# 11_USB_2.net
KiCad netlist of a schematic drawn in Altium Designer
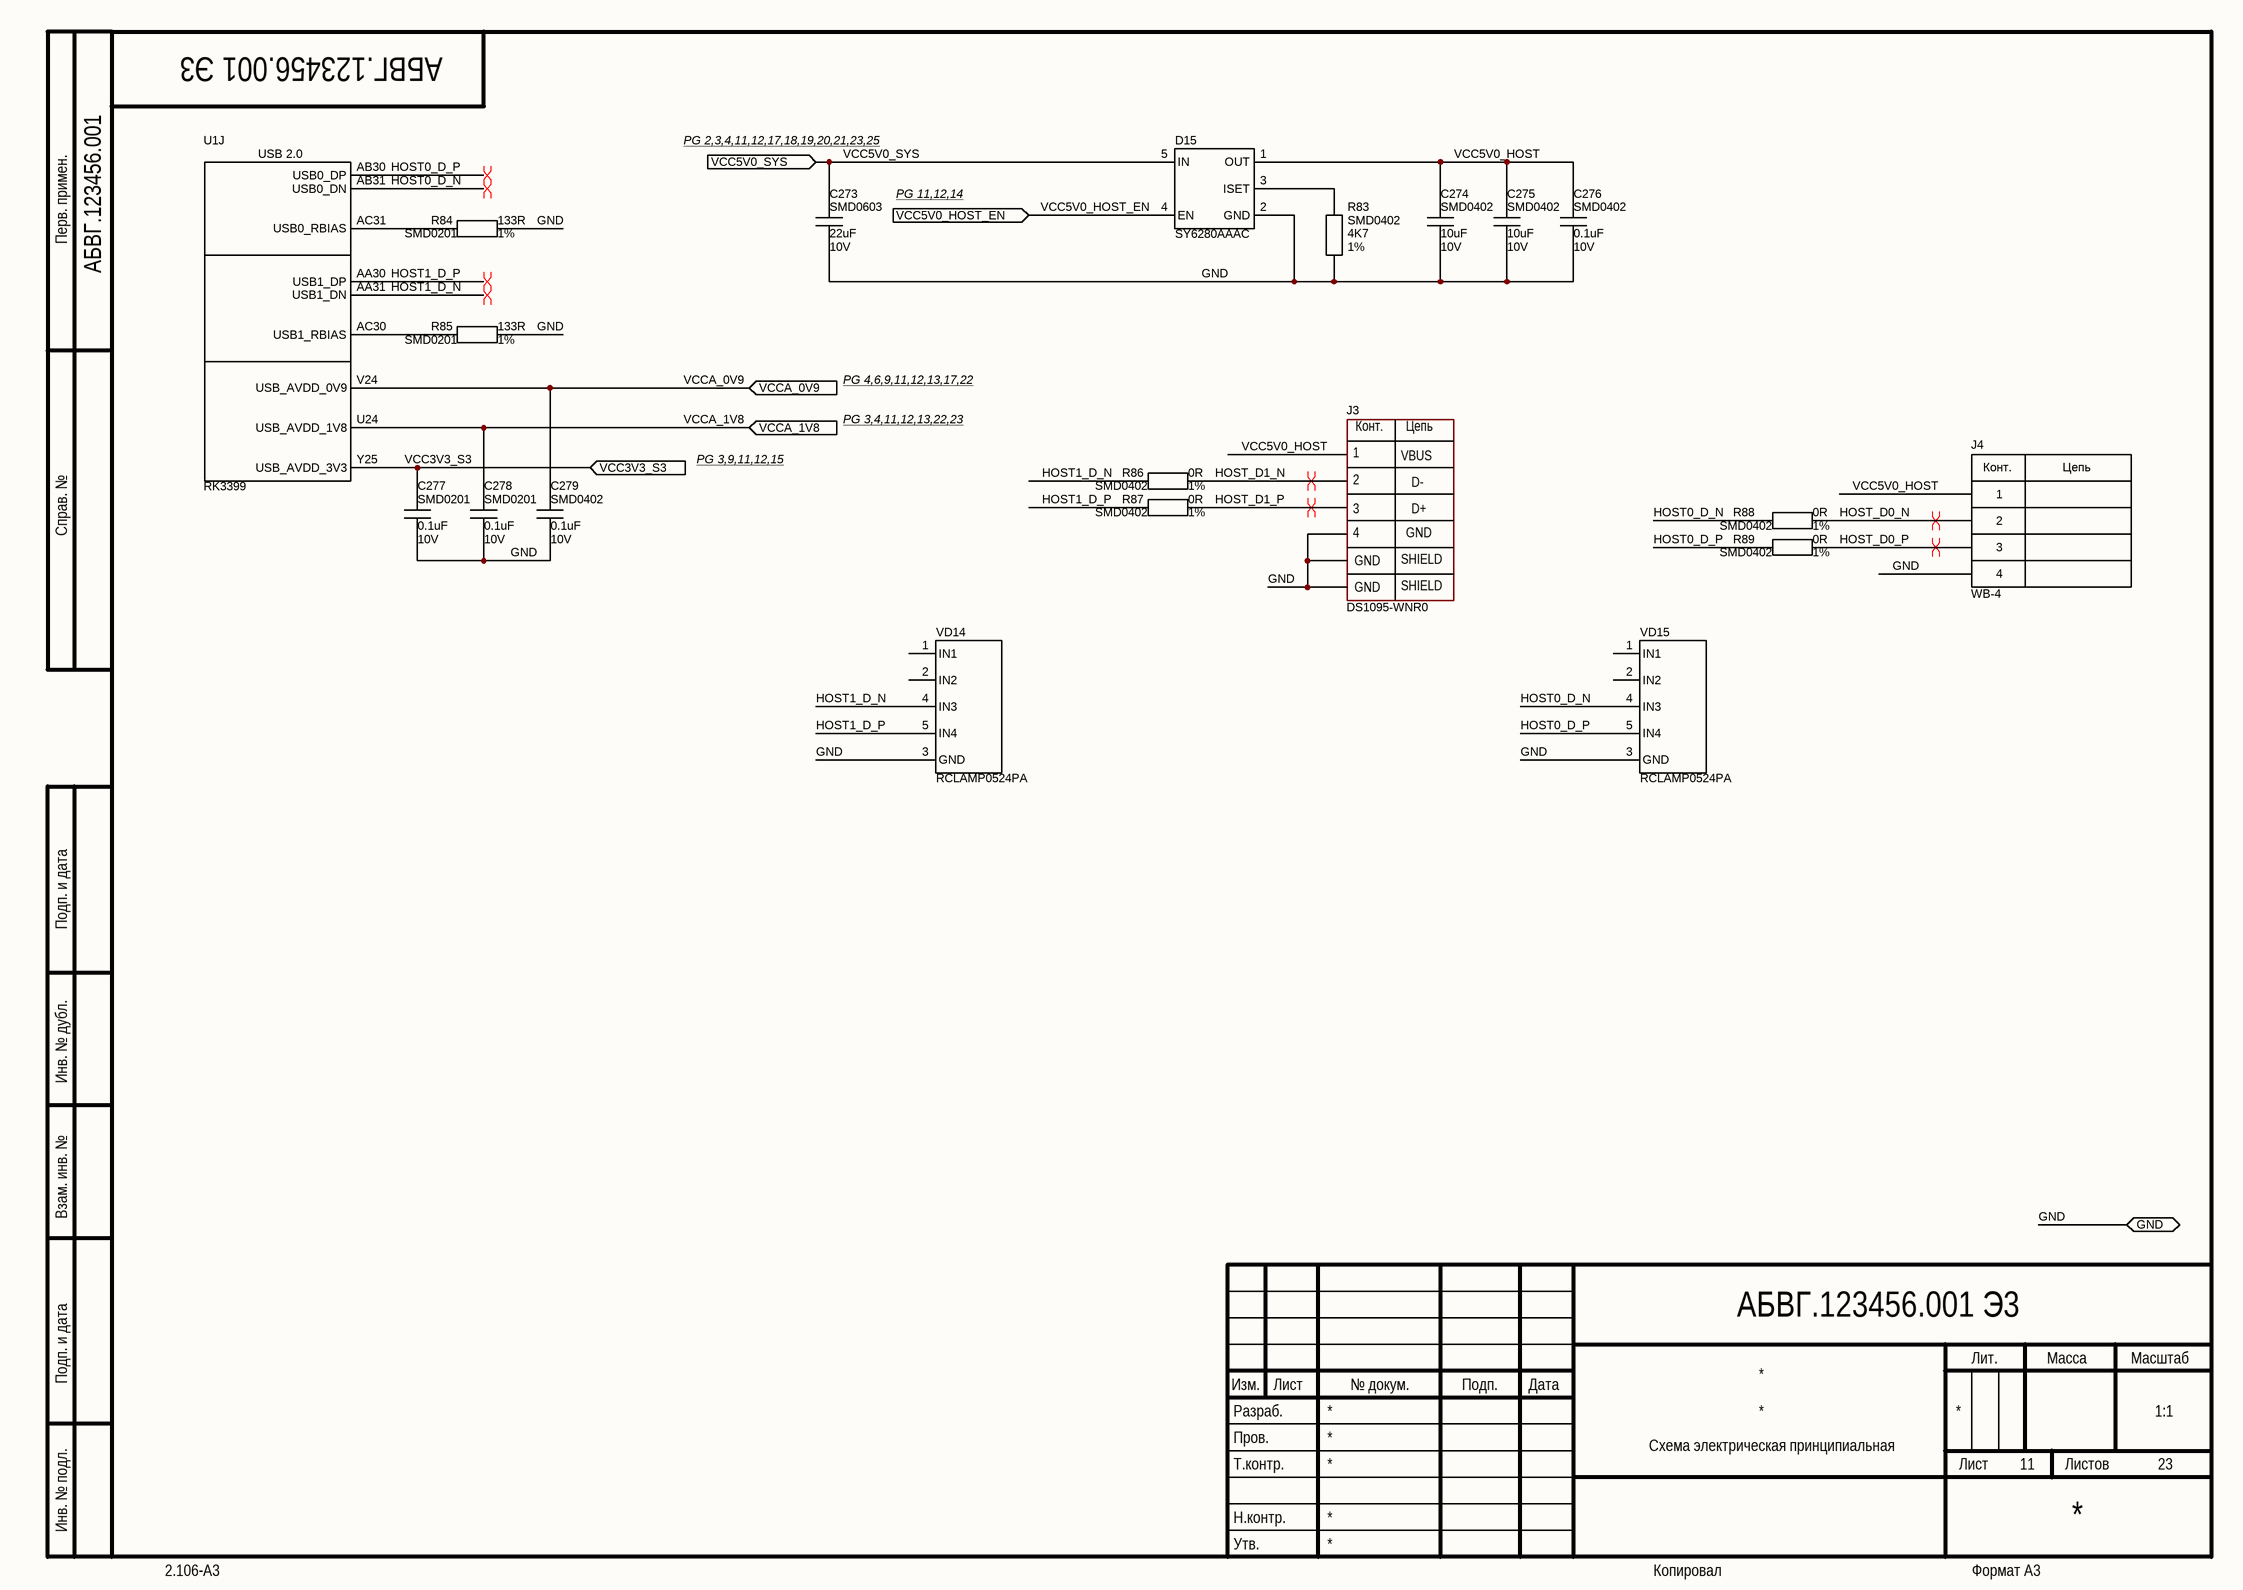
[diagram p0: 11 USB_2.SchDoc]

(export (version "E")
  (design (tool "Eeschema 10.0.6"))
  (components
    (comp (ref "C273")
      (value "22uF")
      (footprint "CAP_SMD_0603")
      (fields
        (field (name "PACKAGE") "SMD0603")
        (field (name "PARTNUMBER") "CL10A226MP8NUNE")
        (field (name "VOLTAGE") "10V")
      )
      (libsource (lib "Didur_SchLib_1") (part "Ceramic_Cap"))
    )
    (comp (ref "C274")
      (value "10uF")
      (footprint "Didur_PcbLib_1:CAP_SMD_0402")
      (fields
        (field (name "PACKAGE") "SMD0402")
        (field (name "PARTNUMBER") "CC0402MRX5R6BB106")
        (field (name "VOLTAGE") "10V")
      )
      (libsource (lib "Didur_SchLib_1") (part "Ceramic_Cap"))
    )
    (comp (ref "C275")
      (value "10uF")
      (footprint "Didur_PcbLib_1:CAP_SMD_0402")
      (fields
        (field (name "PACKAGE") "SMD0402")
        (field (name "PARTNUMBER") "CC0402MRX5R6BB106")
        (field (name "VOLTAGE") "10V")
      )
      (libsource (lib "Didur_SchLib_1") (part "Ceramic_Cap"))
    )
    (comp (ref "C276")
      (value "0.1uF")
      (footprint "Didur_PcbLib_1:CAP_SMD_0402")
      (fields
        (field (name "PACKAGE") "SMD0402")
        (field (name "PARTNUMBER") "CC0402KRX5R6BB104")
        (field (name "VOLTAGE") "10V")
      )
      (libsource (lib "Didur_SchLib_1") (part "Ceramic_Cap"))
    )
    (comp (ref "C277")
      (value "0.1uF")
      (footprint "Didur_PcbLib_1:CAP_SMD_0201")
      (fields
        (field (name "PACKAGE") "SMD0201")
        (field (name "PARTNUMBER") "CC0201KRX5R6BB104")
        (field (name "VOLTAGE") "10V")
      )
      (libsource (lib "Didur_SchLib_1") (part "Ceramic_Cap"))
    )
    (comp (ref "C278")
      (value "0.1uF")
      (footprint "Didur_PcbLib_1:CAP_SMD_0201")
      (fields
        (field (name "PACKAGE") "SMD0201")
        (field (name "PARTNUMBER") "CC0201KRX5R6BB104")
        (field (name "VOLTAGE") "10V")
      )
      (libsource (lib "Didur_SchLib_1") (part "Ceramic_Cap"))
    )
    (comp (ref "C279")
      (value "0.1uF")
      (footprint "Didur_PcbLib_1:CAP_SMD_0402")
      (fields
        (field (name "PACKAGE") "SMD0402")
        (field (name "PARTNUMBER") "CC0402KRX5R6BB104")
        (field (name "VOLTAGE") "10V")
      )
      (libsource (lib "Didur_SchLib_1") (part "Ceramic_Cap"))
    )
    (comp (ref "D15")
      (value "SY6280AAAC")
      (footprint "Didur_PcbLib_1:SOT23-5")
      (libsource (lib "Didur_SchLib_1") (part "SY6280AAAC"))
    )
    (comp (ref "J3")
      (value "DS1095-WNR0")
      (footprint "Didur_PcbLib_1:DS1095-WNR0")
      (libsource (lib "Didur_SchLib_1") (part "USBA-1J"))
    )
    (comp (ref "J4")
      (value "WB-4")
      (footprint "Didur_PcbLib_1:WB-4")
      (fields (field (name "PARTNUMBER") "DS1066-04M(MW-4M)"))
      (libsource (lib "Didur_SchLib_1") (part "CON4"))
    )
    (comp (ref "R83")
      (value "4K7")
      (footprint "Didur_PcbLib_1:RES_SMD_0402")
      (fields
        (field (name "PACKAGE") "SMD0402")
        (field (name "PARTNUMBER") "RC0402FR-074K7L")
        (field (name "TOLERANCE") "1%")
      )
      (libsource (lib "") (part "Chip_Res_1"))
    )
    (comp (ref "R84")
      (value "133R")
      (footprint "Didur_PcbLib_1:RES_SMD_0201")
      (fields
        (field (name "PACKAGE") "SMD0201")
        (field (name "PARTNUMBER") "RC0201FR-07133RL")
        (field (name "TOLERANCE") "1%")
      )
      (libsource (lib "Didur_SchLib_1") (part "Chip_Res"))
    )
    (comp (ref "R85")
      (value "133R")
      (footprint "Didur_PcbLib_1:RES_SMD_0201")
      (fields
        (field (name "PACKAGE") "SMD0201")
        (field (name "PARTNUMBER") "RC0201FR-07133RL")
        (field (name "TOLERANCE") "1%")
      )
      (libsource (lib "Didur_SchLib_1") (part "Chip_Res"))
    )
    (comp (ref "R86")
      (value "0R")
      (footprint "Didur_PcbLib_1:RES_SMD_0402")
      (fields
        (field (name "PACKAGE") "SMD0402")
        (field (name "PARTNUMBER") "RC0402FR-070RL")
        (field (name "TOLERANCE") "1%")
      )
      (libsource (lib "") (part "Chip_Res_2"))
    )
    (comp (ref "R87")
      (value "0R")
      (footprint "Didur_PcbLib_1:RES_SMD_0402")
      (fields
        (field (name "PACKAGE") "SMD0402")
        (field (name "PARTNUMBER") "RC0402FR-070RL")
        (field (name "TOLERANCE") "1%")
      )
      (libsource (lib "") (part "Chip_Res_2"))
    )
    (comp (ref "R88")
      (value "0R")
      (footprint "Didur_PcbLib_1:RES_SMD_0402")
      (fields
        (field (name "PACKAGE") "SMD0402")
        (field (name "PARTNUMBER") "RC0402FR-070RL")
        (field (name "TOLERANCE") "1%")
      )
      (libsource (lib "") (part "Chip_Res_2"))
    )
    (comp (ref "R89")
      (value "0R")
      (footprint "Didur_PcbLib_1:RES_SMD_0402")
      (fields
        (field (name "PACKAGE") "SMD0402")
        (field (name "PARTNUMBER") "RC0402FR-070RL")
        (field (name "TOLERANCE") "1%")
      )
      (libsource (lib "") (part "Chip_Res_2"))
    )
    (comp (ref "U1")
      (value "RK3399")
      (footprint "BGA828C65P31X31_2100X2100X161N")
      (fields (field (name "Comment") "RK3399_FF"))
      (libsource (lib "Didur_SchLib_1") (part "RK3399_FF"))
    )
    (comp (ref "VD14")
      (value "RCLAMP0524PA")
      (footprint "Didur_PcbLib_1:RCLAMP0524PA")
      (libsource (lib "Didur_SchLib_1") (part "RCLAMP0524PA"))
    )
    (comp (ref "VD15")
      (value "RCLAMP0524PA")
      (footprint "Didur_PcbLib_1:RCLAMP0524PA")
      (libsource (lib "Didur_SchLib_1") (part "RCLAMP0524PA"))
    )
  )
  (nets
    (net (code "1") (name "/GND") (class "Default")
      (node (ref "C273") (pin "1") (pinfunction "1_1") (pintype "power_in"))
      (node (ref "C274") (pin "2") (pinfunction "2_2") (pintype "power_in"))
      (node (ref "C275") (pin "2") (pinfunction "2_2") (pintype "power_in"))
      (node (ref "C276") (pin "2") (pinfunction "2_2") (pintype "power_in"))
      (node (ref "C277") (pin "2") (pinfunction "2_2") (pintype "power_in"))
      (node (ref "C278") (pin "2") (pinfunction "2_2") (pintype "power_in"))
      (node (ref "C279") (pin "2") (pinfunction "2_2") (pintype "power_in"))
      (node (ref "D15") (pin "2") (pinfunction "GND_2") (pintype "passive"))
      (node (ref "J3") (pin "4") (pinfunction "4_4") (pintype "passive"))
      (node (ref "J3") (pin "S1") (pinfunction "GND_S1") (pintype "passive"))
      (node (ref "J3") (pin "S2") (pinfunction "GND_S2") (pintype "passive"))
      (node (ref "J4") (pin "4") (pinfunction "4_4") (pintype "power_in"))
      (node (ref "R83") (pin "2") (pinfunction "2_2") (pintype "passive"))
      (node (ref "R84") (pin "1") (pinfunction "1_1") (pintype "passive"))
      (node (ref "R85") (pin "1") (pinfunction "1_1") (pintype "passive"))
      (node (ref "VD14") (pin "3") (pinfunction "GND_3") (pintype "passive"))
      (node (ref "VD15") (pin "3") (pinfunction "GND_3") (pintype "passive"))
    )
    (net (code "2") (name "/HOST0_D_N") (class "Default")
      (node (ref "R88") (pin "1") (pinfunction "1_1") (pintype "passive"))
      (node (ref "U1") (pin "AB31") (pinfunction "USB0_DN_AB31") (pintype "passive"))
      (node (ref "VD15") (pin "4") (pinfunction "IN3_4") (pintype "passive"))
    )
    (net (code "3") (name "/HOST0_D_P") (class "Default")
      (node (ref "R89") (pin "1") (pinfunction "1_1") (pintype "passive"))
      (node (ref "U1") (pin "AB30") (pinfunction "USB0_DP_AB30") (pintype "passive"))
      (node (ref "VD15") (pin "5") (pinfunction "IN4_5") (pintype "passive"))
    )
    (net (code "4") (name "/HOST1_D_N") (class "Default")
      (node (ref "R86") (pin "1") (pinfunction "1_1") (pintype "passive"))
      (node (ref "U1") (pin "AA31") (pinfunction "USB1_DN_AA31") (pintype "passive"))
      (node (ref "VD14") (pin "4") (pinfunction "IN3_4") (pintype "passive"))
    )
    (net (code "5") (name "/HOST1_D_P") (class "Default")
      (node (ref "R87") (pin "1") (pinfunction "1_1") (pintype "passive"))
      (node (ref "U1") (pin "AA30") (pinfunction "USB1_DP_AA30") (pintype "passive"))
      (node (ref "VD14") (pin "5") (pinfunction "IN4_5") (pintype "passive"))
    )
    (net (code "6") (name "/HOST_D0_N") (class "Default")
      (node (ref "J4") (pin "2") (pinfunction "2_2") (pintype "passive"))
      (node (ref "R88") (pin "2") (pinfunction "2_2") (pintype "passive"))
    )
    (net (code "7") (name "/HOST_D0_P") (class "Default")
      (node (ref "J4") (pin "3") (pinfunction "3_3") (pintype "power_in"))
      (node (ref "R89") (pin "2") (pinfunction "2_2") (pintype "passive"))
    )
    (net (code "8") (name "/HOST_D1_N") (class "Default")
      (node (ref "J3") (pin "2") (pinfunction "2_2") (pintype "passive"))
      (node (ref "R86") (pin "2") (pinfunction "2_2") (pintype "passive"))
    )
    (net (code "9") (name "/HOST_D1_P") (class "Default")
      (node (ref "J3") (pin "3") (pinfunction "3_3") (pintype "passive"))
      (node (ref "R87") (pin "2") (pinfunction "2_2") (pintype "passive"))
    )
    (net (code "10") (name "/VCC3V3_S3") (class "Default")
      (node (ref "C277") (pin "1") (pinfunction "1_1") (pintype "power_in"))
      (node (ref "U1") (pin "Y25") (pinfunction "USB_AVDD_3V3_Y25") (pintype "passive"))
    )
    (net (code "11") (name "/VCC5V0_HOST") (class "Default")
      (node (ref "C274") (pin "1") (pinfunction "1_1") (pintype "power_in"))
      (node (ref "C275") (pin "1") (pinfunction "1_1") (pintype "power_in"))
      (node (ref "C276") (pin "1") (pinfunction "1_1") (pintype "power_in"))
      (node (ref "D15") (pin "1") (pinfunction "OUT_1") (pintype "passive"))
      (node (ref "J3") (pin "1") (pintype "passive"))
      (node (ref "J4") (pin "1") (pinfunction "1_1") (pintype "passive"))
    )
    (net (code "12") (name "/VCC5V0_HOST_EN") (class "Default")
      (node (ref "D15") (pin "4") (pinfunction "EN_4") (pintype "passive"))
    )
    (net (code "13") (name "/VCC5V0_SYS") (class "Default")
      (node (ref "C273") (pin "2") (pinfunction "2_2") (pintype "power_in"))
      (node (ref "D15") (pin "5") (pinfunction "IN_5") (pintype "passive"))
    )
    (net (code "14") (name "/VCCA_0V9") (class "Default")
      (node (ref "C279") (pin "1") (pinfunction "1_1") (pintype "power_in"))
      (node (ref "U1") (pin "V24") (pinfunction "USB_AVDD_0V9_V24") (pintype "passive"))
    )
    (net (code "15") (name "/VCCA_1V8") (class "Default")
      (node (ref "C278") (pin "1") (pinfunction "1_1") (pintype "power_in"))
      (node (ref "U1") (pin "U24") (pinfunction "USB_AVDD_1V8_U24") (pintype "passive"))
    )
    (net (code "16") (name "Net-(D15-ISET)") (class "Default")
      (node (ref "D15") (pin "3") (pinfunction "ISET_3") (pintype "passive"))
      (node (ref "R83") (pin "1") (pinfunction "1_1") (pintype "passive"))
    )
    (net (code "17") (name "Net-(U1J-USB0_RBIAS)") (class "Default")
      (node (ref "R84") (pin "2") (pinfunction "2_2") (pintype "passive"))
      (node (ref "U1") (pin "AC31") (pinfunction "USB0_RBIAS_AC31") (pintype "passive"))
    )
    (net (code "18") (name "Net-(U1J-USB1_RBIAS)") (class "Default")
      (node (ref "R85") (pin "2") (pinfunction "2_2") (pintype "passive"))
      (node (ref "U1") (pin "AC30") (pinfunction "USB1_RBIAS_AC30") (pintype "passive"))
    )
    (net (code "19") (name "unconnected-(VD14-IN1-Pad1)") (class "Default")
      (node (ref "VD14") (pin "1") (pinfunction "IN1_1") (pintype "passive"))
    )
    (net (code "20") (name "unconnected-(VD14-IN2-Pad2)") (class "Default")
      (node (ref "VD14") (pin "2") (pinfunction "IN2_2") (pintype "passive"))
    )
    (net (code "21") (name "unconnected-(VD15-IN1-Pad1)") (class "Default")
      (node (ref "VD15") (pin "1") (pinfunction "IN1_1") (pintype "passive"))
    )
    (net (code "22") (name "unconnected-(VD15-IN2-Pad2)") (class "Default")
      (node (ref "VD15") (pin "2") (pinfunction "IN2_2") (pintype "passive"))
    )
  )
)
